# nse5310-module.net
KiCad netlist of a schematic drawn in Altium Designer
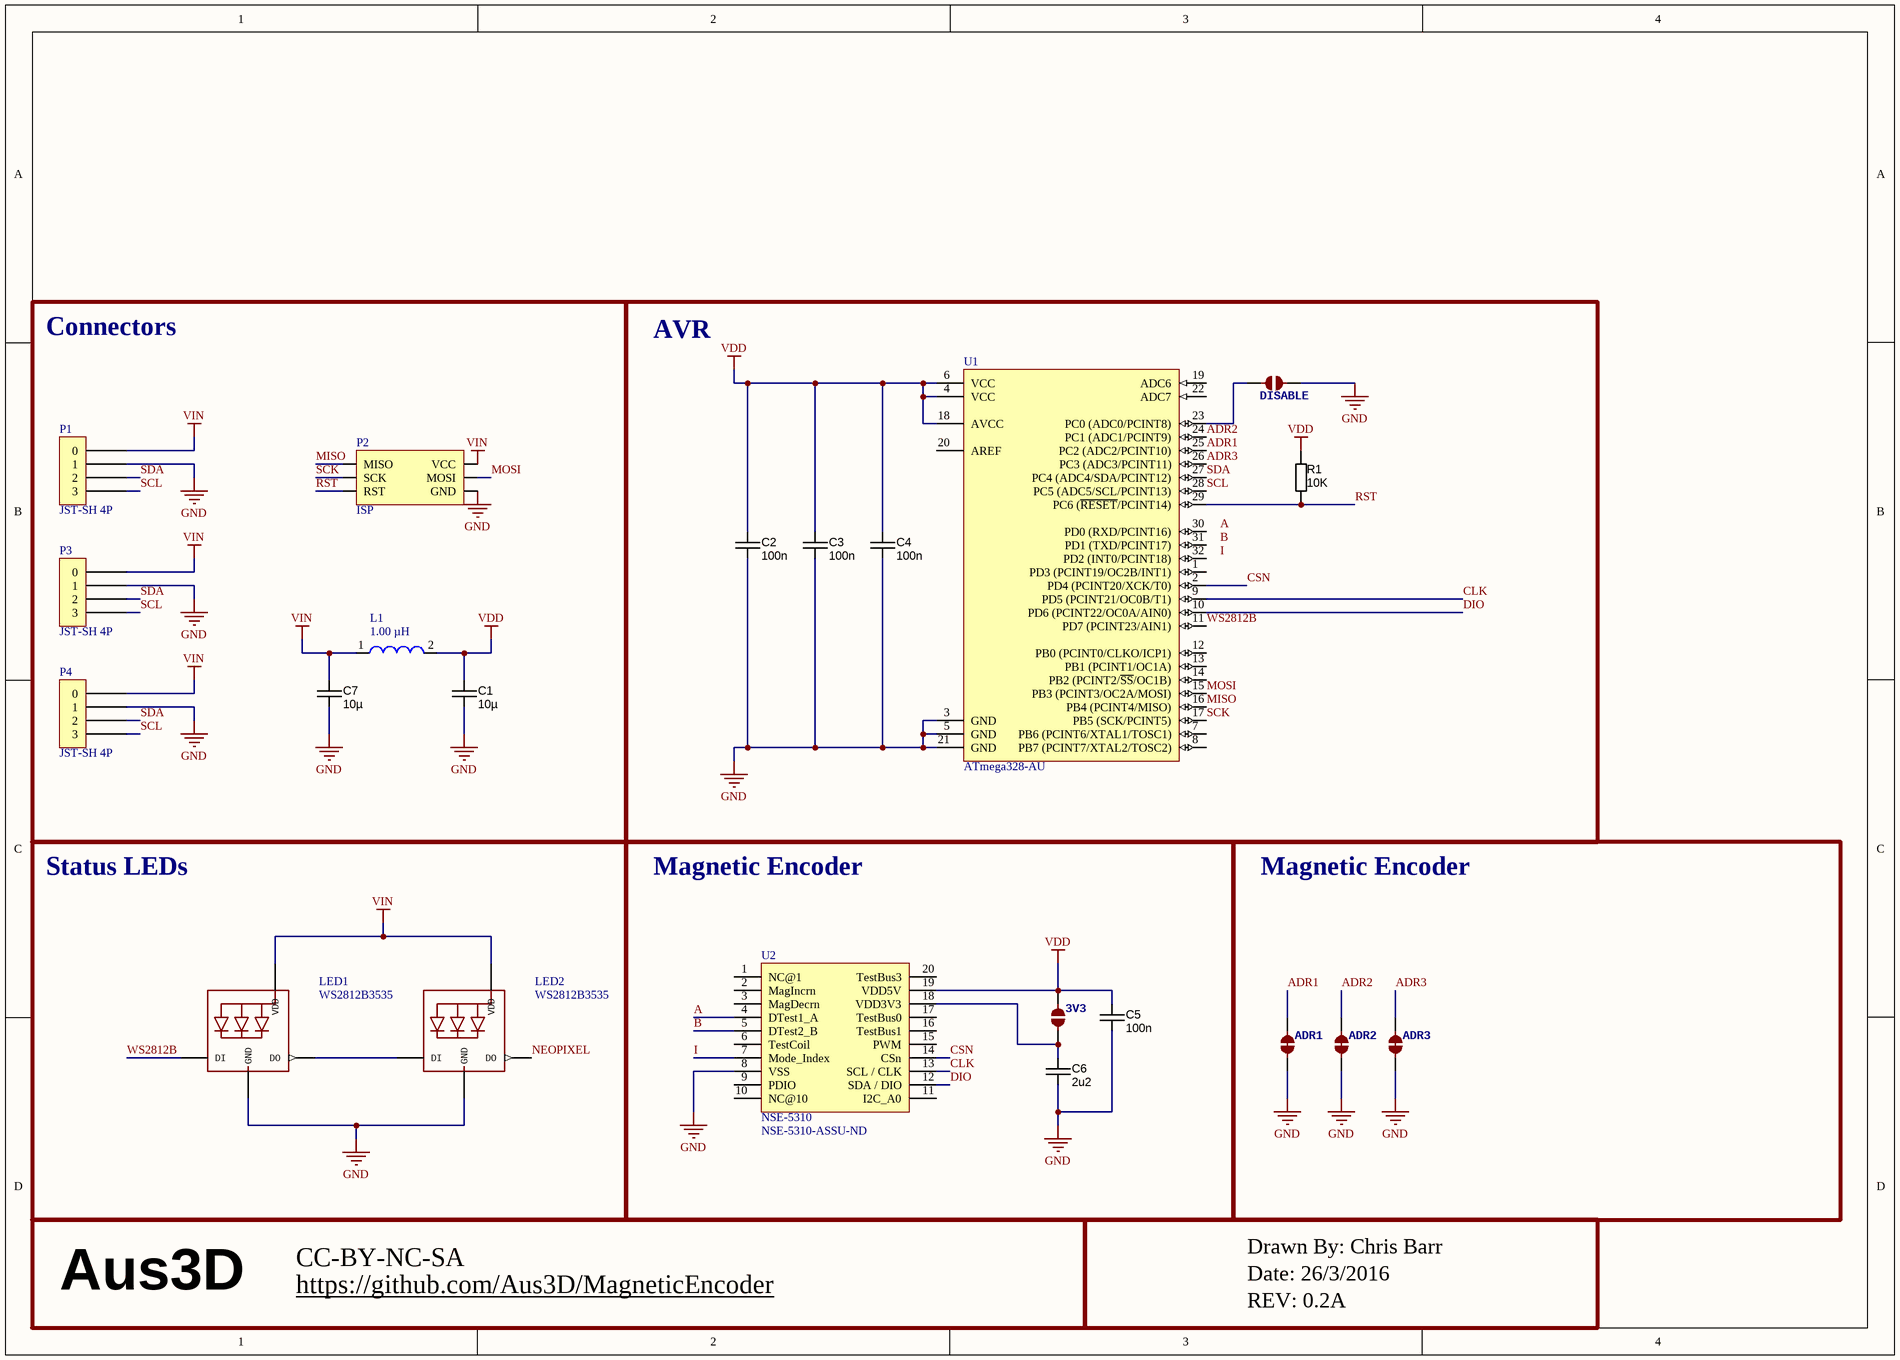
[diagram p0: nse5310-module.SchDoc]

(export (version "E")
  (design (tool "Eeschema 10.0.6"))
  (components
    (comp (ref "3V3")
      (value "JUMPER-PAD-2-NO")
      (footprint "PAD-JUMPER-2-NO_NO_SILK")
      (libsource (lib "SparkFun-Passives") (part "JUMPER-PAD-2-NO"))
    )
    (comp (ref "ADR1")
      (value "JUMPER-PAD-2-NC_BY_TRACE")
      (footprint "PAD-JUMPER-2-NC_BY_TRACE_YES_SILK")
      (libsource (lib "SparkFun-Passives") (part "JUMPER-PAD-2-NC_BY_TRACE"))
    )
    (comp (ref "ADR2")
      (value "JUMPER-PAD-2-NC_BY_TRACE")
      (footprint "PAD-JUMPER-2-NC_BY_TRACE_YES_SILK")
      (libsource (lib "SparkFun-Passives") (part "JUMPER-PAD-2-NC_BY_TRACE"))
    )
    (comp (ref "ADR3")
      (value "JUMPER-PAD-2-NC_BY_TRACE")
      (footprint "PAD-JUMPER-2-NC_BY_TRACE_YES_SILK")
      (libsource (lib "SparkFun-Passives") (part "JUMPER-PAD-2-NC_BY_TRACE"))
    )
    (comp (ref "C1")
      (value "10µ")
      (footprint "CAPC2012X135N")
      (description "Capacitor SMD Cer 10uF 10% 10V X5R 0805")
      (fields (field (name "TOLERANCE") "±10%") (field (name "Comment") "approved sub OK"))
      (libsource (lib "PBL - Capacitors") (part "CAPC_10u_0805_10V"))
    )
    (comp (ref "C2")
      (value "100n")
      (footprint "CAPC1608X90N")
      (description "Capacitor SMD Cer 100nF 10% 50V X7R 0603")
      (fields (field (name "TOLERANCE") "±10%") (field (name "Comment") "approved sub OK"))
      (libsource (lib "PBL - Capacitors") (part "CAPC_100n_0603_X7R_50V_10%"))
    )
    (comp (ref "C3")
      (value "100n")
      (footprint "CAPC1608X90N")
      (description "Capacitor SMD Cer 100nF 10% 50V X7R 0603")
      (fields (field (name "TOLERANCE") "±10%") (field (name "Comment") "approved sub OK"))
      (libsource (lib "PBL - Capacitors") (part "CAPC_100n_0603_X7R_50V_10%"))
    )
    (comp (ref "C4")
      (value "100n")
      (footprint "CAPC1608X90N")
      (description "Capacitor SMD Cer 100nF 10% 50V X7R 0603")
      (fields (field (name "TOLERANCE") "±10%") (field (name "Comment") "approved sub OK"))
      (libsource (lib "PBL - Capacitors") (part "CAPC_100n_0603_X7R_50V_10%"))
    )
    (comp (ref "C5")
      (value "100n")
      (footprint "CAPC1608X90N")
      (description "Capacitor SMD Cer 100nF 10% 50V X7R 0603")
      (fields (field (name "TOLERANCE") "±10%") (field (name "Comment") "approved sub OK"))
      (libsource (lib "PBL - Capacitors") (part "CAPC_100n_0603_X7R_50V_10%"))
    )
    (comp (ref "C6")
      (value "2u2")
      (footprint "CAPC1608X90N")
      (description "Capacitor SMD Cer 2.2uF 10% 10V X5R 0603")
      (fields (field (name "TOLERANCE") "±10%") (field (name "Comment") "approved sub OK"))
      (libsource (lib "PBL - Capacitors") (part "CAPC_2u2_0603_10V_10%"))
    )
    (comp (ref "C7")
      (value "10µ")
      (footprint "CAPC2012X135N")
      (description "Capacitor SMD Cer 10uF 10% 10V X5R 0805")
      (fields (field (name "TOLERANCE") "±10%") (field (name "Comment") "approved sub OK"))
      (libsource (lib "PBL - Capacitors") (part "CAPC_10u_0805_10V"))
    )
    (comp (ref "DISABLE")
      (value "JUMPER-PAD-2-NO")
      (footprint "PAD-JUMPER-2-NO_NO_SILK")
      (libsource (lib "SparkFun-Passives") (part "JUMPER-PAD-2-NO"))
    )
    (comp (ref "L1")
      (value "7447965")
      (footprint "RESC1608X55N")
      (description "SMD-Multilayer Inductor WE-MI, L = 1.00 µH")
      (fields (field (name "INDUCTANCE") "1.00 µH"))
      (libsource (lib "Filter Inductor") (part "7447965"))
    )
    (comp (ref "LED1")
      (value "WS2812B3535")
      (footprint "LED3535")
      (libsource (lib "adafruit") (part "WS2812B3535"))
    )
    (comp (ref "LED2")
      (value "WS2812B3535")
      (footprint "LED3535")
      (libsource (lib "adafruit") (part "WS2812B3535"))
    )
    (comp (ref "P1")
      (value "JST-SH 4P")
      (footprint "SM04B-SRSS-TB")
      (libsource (lib "Schlib1") (part "SM04B-SRSS-TB"))
    )
    (comp (ref "P2")
      (value "ISP")
      (footprint "ICSP Pads - SMD")
      (libsource (lib "Schlib1") (part "ISP Header"))
    )
    (comp (ref "P3")
      (value "JST-SH 4P")
      (footprint "SM04B-SRSS-TB")
      (libsource (lib "Schlib1") (part "SM04B-SRSS-TB"))
    )
    (comp (ref "P4")
      (value "JST-SH 4P")
      (footprint "SM04B-SRSS-TB")
      (libsource (lib "Schlib1") (part "SM04B-SRSS-TB"))
    )
    (comp (ref "R1")
      (value "10K")
      (footprint "RESC1608X55N")
      (description "Resistor SMD chip 10k Ohm 0.1W 5% 0603")
      (fields (field (name "TOLERANCE") "±5%") (field (name "Comment") "Thick Film"))
      (libsource (lib "PBL - Resistors") (part "RES_10K_0603_5%"))
    )
    (comp (ref "U1")
      (value "ATmega328-AU")
      (footprint "32A_N")
      (libsource (lib "Atmel Microcontroller megaAVR") (part "ATmega328-AU"))
    )
    (comp (ref "U2")
      (value "NSE-5310")
      (footprint "NSE-5310")
      (fields (field (name "SUPPLIER PART NUMBER 1") "NSE-5310-ASSU-ND"))
      (libsource (lib "Schlib1") (part "NSE-5310"))
    )
  )
  (nets
    (net (code "1") (name "/A") (class "Default")
      (node (ref "U2") (pin "4") (pinfunction "DTest1_A_4") (pintype "passive"))
    )
    (net (code "2") (name "/ADR1") (class "Default")
      (node (ref "ADR1") (pin "2") (pinfunction "2_2") (pintype "passive"))
      (node (ref "U1") (pin "25") (pinfunction "PC2_(ADC2/PCINT10)_25") (pintype "bidirectional"))
    )
    (net (code "3") (name "/ADR2") (class "Default")
      (node (ref "ADR2") (pin "2") (pinfunction "2_2") (pintype "passive"))
      (node (ref "U1") (pin "24") (pinfunction "PC1_(ADC1/PCINT9)_24") (pintype "bidirectional"))
    )
    (net (code "4") (name "/ADR3") (class "Default")
      (node (ref "ADR3") (pin "2") (pinfunction "2_2") (pintype "passive"))
      (node (ref "U1") (pin "26") (pinfunction "PC3_(ADC3/PCINT11)_26") (pintype "bidirectional"))
    )
    (net (code "5") (name "/B") (class "Default")
      (node (ref "U2") (pin "5") (pinfunction "DTest2_B_5") (pintype "passive"))
    )
    (net (code "6") (name "/CLK") (class "Default")
      (node (ref "U1") (pin "9") (pinfunction "PD5_(PCINT21/OC0B/T1)_9") (pintype "bidirectional"))
      (node (ref "U2") (pin "13") (pinfunction "SCL_/_CLK_13") (pintype "passive"))
    )
    (net (code "7") (name "/CSN") (class "Default")
      (node (ref "U1") (pin "2") (pinfunction "PD4_(PCINT20/XCK/T0)_2") (pintype "bidirectional"))
      (node (ref "U2") (pin "14") (pinfunction "CSn_14") (pintype "passive"))
    )
    (net (code "8") (name "/DIO") (class "Default")
      (node (ref "U1") (pin "10") (pinfunction "PD6_(PCINT22/OC0A/AIN0)_10") (pintype "bidirectional"))
      (node (ref "U2") (pin "12") (pinfunction "SDA_/_DIO_12") (pintype "passive"))
    )
    (net (code "9") (name "/I") (class "Default")
      (node (ref "U2") (pin "7") (pinfunction "Mode_Index_7") (pintype "passive"))
    )
    (net (code "10") (name "/MISO") (class "Default")
      (node (ref "P2") (pin "0") (pinfunction "MISO_0") (pintype "passive"))
      (node (ref "U1") (pin "16") (pinfunction "PB4_(PCINT4/MISO)_16") (pintype "bidirectional"))
    )
    (net (code "11") (name "/MOSI") (class "Default")
      (node (ref "P2") (pin "3") (pinfunction "MOSI_3") (pintype "passive"))
      (node (ref "U1") (pin "15") (pinfunction "PB3_(PCINT3/OC2A/MOSI)_15") (pintype "bidirectional"))
    )
    (net (code "12") (name "/NEOPIXEL") (class "Default")
      (node (ref "LED2") (pin "3") (pinfunction "DO_3") (pintype "output"))
    )
    (net (code "13") (name "/RST") (class "Default")
      (node (ref "P2") (pin "4") (pinfunction "RST_4") (pintype "passive"))
      (node (ref "R1") (pin "2") (pinfunction "2_2") (pintype "passive"))
      (node (ref "U1") (pin "29") (pinfunction "PC6_(~{RESET}/PCINT14)_29") (pintype "bidirectional"))
    )
    (net (code "14") (name "/SCK") (class "Default")
      (node (ref "P2") (pin "2") (pinfunction "SCK_2") (pintype "passive"))
      (node (ref "U1") (pin "17") (pinfunction "PB5_(SCK/PCINT5)_17") (pintype "bidirectional"))
    )
    (net (code "15") (name "/SCL") (class "Default")
      (node (ref "P1") (pin "3") (pinfunction "3_3") (pintype "passive"))
      (node (ref "P3") (pin "3") (pinfunction "3_3") (pintype "passive"))
      (node (ref "P4") (pin "3") (pinfunction "3_3") (pintype "passive"))
      (node (ref "U1") (pin "28") (pinfunction "PC5_(ADC5/SCL/PCINT13)_28") (pintype "bidirectional"))
    )
    (net (code "16") (name "/SDA") (class "Default")
      (node (ref "P1") (pin "2") (pinfunction "2_2") (pintype "passive"))
      (node (ref "P3") (pin "2") (pinfunction "2_2") (pintype "passive"))
      (node (ref "P4") (pin "2") (pinfunction "2_2") (pintype "passive"))
      (node (ref "U1") (pin "27") (pinfunction "PC4_(ADC4/SDA/PCINT12)_27") (pintype "bidirectional"))
    )
    (net (code "17") (name "/WS2812B") (class "Default")
      (node (ref "LED1") (pin "1") (pinfunction "DI_1") (pintype "passive"))
      (node (ref "U1") (pin "11") (pinfunction "PD7_(PCINT23/AIN1)_11") (pintype "bidirectional"))
    )
    (net (code "18") (name "GND") (class "Default")
      (node (ref "ADR1") (pin "1") (pinfunction "1_1") (pintype "passive"))
      (node (ref "ADR2") (pin "1") (pinfunction "1_1") (pintype "passive"))
      (node (ref "ADR3") (pin "1") (pinfunction "1_1") (pintype "passive"))
      (node (ref "C1") (pin "2") (pintype "passive"))
      (node (ref "C2") (pin "2") (pintype "passive"))
      (node (ref "C3") (pin "2") (pintype "passive"))
      (node (ref "C4") (pin "2") (pintype "passive"))
      (node (ref "C5") (pin "2") (pintype "passive"))
      (node (ref "C6") (pin "2") (pintype "passive"))
      (node (ref "C7") (pin "2") (pintype "passive"))
      (node (ref "DISABLE") (pin "1") (pinfunction "1_1") (pintype "passive"))
      (node (ref "LED1") (pin "4") (pinfunction "GND_4") (pintype "power_in"))
      (node (ref "LED2") (pin "4") (pinfunction "GND_4") (pintype "power_in"))
      (node (ref "P1") (pin "1") (pinfunction "1_1") (pintype "passive"))
      (node (ref "P2") (pin "5") (pinfunction "GND_5") (pintype "passive"))
      (node (ref "P3") (pin "1") (pinfunction "1_1") (pintype "passive"))
      (node (ref "P4") (pin "1") (pinfunction "1_1") (pintype "passive"))
      (node (ref "U1") (pin "21") (pinfunction "GND_21") (pintype "power_in"))
      (node (ref "U1") (pin "3") (pinfunction "GND_3") (pintype "power_in"))
      (node (ref "U1") (pin "5") (pinfunction "GND_5") (pintype "power_in"))
      (node (ref "U2") (pin "8") (pinfunction "VSS_8") (pintype "passive"))
    )
    (net (code "19") (name "Net-(LED1-DO)") (class "Default")
      (node (ref "LED1") (pin "3") (pinfunction "DO_3") (pintype "output"))
      (node (ref "LED2") (pin "1") (pinfunction "DI_1") (pintype "passive"))
    )
    (net (code "20") (name "Net-(U1-PC0_(ADC0{slash}PCINT8))") (class "Default")
      (node (ref "DISABLE") (pin "2") (pinfunction "2_2") (pintype "passive"))
      (node (ref "U1") (pin "23") (pinfunction "PC0_(ADC0/PCINT8)_23") (pintype "bidirectional"))
    )
    (net (code "21") (name "Net-(U2-VDD3V3)") (class "Default")
      (node (ref "3V3") (pin "1") (pinfunction "1_1") (pintype "passive"))
      (node (ref "C6") (pin "1") (pintype "passive"))
      (node (ref "U2") (pin "18") (pinfunction "VDD3V3_18") (pintype "passive"))
    )
    (net (code "22") (name "VDD") (class "Default")
      (node (ref "3V3") (pin "2") (pinfunction "2_2") (pintype "passive"))
      (node (ref "C1") (pin "1") (pintype "passive"))
      (node (ref "C2") (pin "1") (pintype "passive"))
      (node (ref "C3") (pin "1") (pintype "passive"))
      (node (ref "C4") (pin "1") (pintype "passive"))
      (node (ref "C5") (pin "1") (pintype "passive"))
      (node (ref "L1") (pin "2") (pinfunction "2_2") (pintype "passive"))
      (node (ref "R1") (pin "1") (pinfunction "1_1") (pintype "passive"))
      (node (ref "U1") (pin "18") (pinfunction "AVCC_18") (pintype "power_in"))
      (node (ref "U1") (pin "4") (pinfunction "VCC_4") (pintype "power_in"))
      (node (ref "U1") (pin "6") (pinfunction "VCC_6") (pintype "power_in"))
      (node (ref "U2") (pin "19") (pinfunction "VDD5V_19") (pintype "passive"))
    )
    (net (code "23") (name "VIN") (class "Default")
      (node (ref "C7") (pin "1") (pintype "passive"))
      (node (ref "L1") (pin "1") (pinfunction "1_1") (pintype "passive"))
      (node (ref "LED1") (pin "2") (pinfunction "VDD_2") (pintype "power_in"))
      (node (ref "LED2") (pin "2") (pinfunction "VDD_2") (pintype "power_in"))
      (node (ref "P1") (pin "0") (pinfunction "0_0") (pintype "passive"))
      (node (ref "P2") (pin "1") (pinfunction "VCC_1") (pintype "passive"))
      (node (ref "P3") (pin "0") (pinfunction "0_0") (pintype "passive"))
      (node (ref "P4") (pin "0") (pinfunction "0_0") (pintype "passive"))
    )
    (net (code "24") (name "unconnected-(U1-ADC6-Pad19)") (class "Default")
      (node (ref "U1") (pin "19") (pinfunction "ADC6_19") (pintype "input"))
    )
    (net (code "25") (name "unconnected-(U1-ADC7-Pad22)") (class "Default")
      (node (ref "U1") (pin "22") (pinfunction "ADC7_22") (pintype "input"))
    )
    (net (code "26") (name "unconnected-(U1-AREF-Pad20)") (class "Default")
      (node (ref "U1") (pin "20") (pinfunction "AREF_20") (pintype "passive"))
    )
    (net (code "27") (name "unconnected-(U1-PB0_(PCINT0{slash}CLKO{slash}ICP1)-Pad12)") (class "Default")
      (node (ref "U1") (pin "12") (pinfunction "PB0_(PCINT0/CLKO/ICP1)_12") (pintype "bidirectional"))
    )
    (net (code "28") (name "unconnected-(U1-PB1_(PCINT1{slash}OC1A)-Pad13)") (class "Default")
      (node (ref "U1") (pin "13") (pinfunction "PB1_(PCINT1/OC1A)_13") (pintype "bidirectional"))
    )
    (net (code "29") (name "unconnected-(U1-PB2_(PCINT2{slash}~{SS}{slash}OC1B)-Pad14)") (class "Default")
      (node (ref "U1") (pin "14") (pinfunction "PB2_(PCINT2/~{SS}/OC1B)_14") (pintype "bidirectional"))
    )
    (net (code "30") (name "unconnected-(U1-PB6_(PCINT6{slash}XTAL1{slash}TOSC1)-Pad7)") (class "Default")
      (node (ref "U1") (pin "7") (pinfunction "PB6_(PCINT6/XTAL1/TOSC1)_7") (pintype "bidirectional"))
    )
    (net (code "31") (name "unconnected-(U1-PB7_(PCINT7{slash}XTAL2{slash}TOSC2)-Pad8)") (class "Default")
      (node (ref "U1") (pin "8") (pinfunction "PB7_(PCINT7/XTAL2/TOSC2)_8") (pintype "bidirectional"))
    )
    (net (code "32") (name "unconnected-(U1-PD0_(RXD{slash}PCINT16)-Pad30)") (class "Default")
      (node (ref "U1") (pin "30") (pinfunction "PD0_(RXD/PCINT16)_30") (pintype "bidirectional"))
    )
    (net (code "33") (name "unconnected-(U1-PD1_(TXD{slash}PCINT17)-Pad31)") (class "Default")
      (node (ref "U1") (pin "31") (pinfunction "PD1_(TXD/PCINT17)_31") (pintype "bidirectional"))
    )
    (net (code "34") (name "unconnected-(U1-PD2_(INT0{slash}PCINT18)-Pad32)") (class "Default")
      (node (ref "U1") (pin "32") (pinfunction "PD2_(INT0/PCINT18)_32") (pintype "bidirectional"))
    )
    (net (code "35") (name "unconnected-(U1-PD3_(PCINT19{slash}OC2B{slash}INT1)-Pad1)") (class "Default")
      (node (ref "U1") (pin "1") (pinfunction "PD3_(PCINT19/OC2B/INT1)_1") (pintype "bidirectional"))
    )
    (net (code "36") (name "unconnected-(U2-I2C_A0-Pad11)") (class "Default")
      (node (ref "U2") (pin "11") (pinfunction "I2C_A0_11") (pintype "passive"))
    )
    (net (code "37") (name "unconnected-(U2-MagDecrn-Pad3)") (class "Default")
      (node (ref "U2") (pin "3") (pinfunction "MagDecrn_3") (pintype "passive"))
    )
    (net (code "38") (name "unconnected-(U2-MagIncrn-Pad2)") (class "Default")
      (node (ref "U2") (pin "2") (pinfunction "MagIncrn_2") (pintype "passive"))
    )
    (net (code "39") (name "unconnected-(U2-NC@1-Pad1)") (class "Default")
      (node (ref "U2") (pin "1") (pinfunction "NC@1_1") (pintype "passive"))
    )
    (net (code "40") (name "unconnected-(U2-NC@10-Pad10)") (class "Default")
      (node (ref "U2") (pin "10") (pinfunction "NC@10_10") (pintype "passive"))
    )
    (net (code "41") (name "unconnected-(U2-PDIO-Pad9)") (class "Default")
      (node (ref "U2") (pin "9") (pinfunction "PDIO_9") (pintype "passive"))
    )
    (net (code "42") (name "unconnected-(U2-PWM-Pad15)") (class "Default")
      (node (ref "U2") (pin "15") (pinfunction "PWM_15") (pintype "passive"))
    )
    (net (code "43") (name "unconnected-(U2-TestBus0-Pad17)") (class "Default")
      (node (ref "U2") (pin "17") (pinfunction "TestBus0_17") (pintype "passive"))
    )
    (net (code "44") (name "unconnected-(U2-TestBus1-Pad16)") (class "Default")
      (node (ref "U2") (pin "16") (pinfunction "TestBus1_16") (pintype "passive"))
    )
    (net (code "45") (name "unconnected-(U2-TestBus3-Pad20)") (class "Default")
      (node (ref "U2") (pin "20") (pinfunction "TestBus3_20") (pintype "passive"))
    )
    (net (code "46") (name "unconnected-(U2-TestCoil-Pad6)") (class "Default")
      (node (ref "U2") (pin "6") (pinfunction "TestCoil_6") (pintype "passive"))
    )
  )
)
